# IR.net
KiCad netlist of a schematic drawn in EAGLE
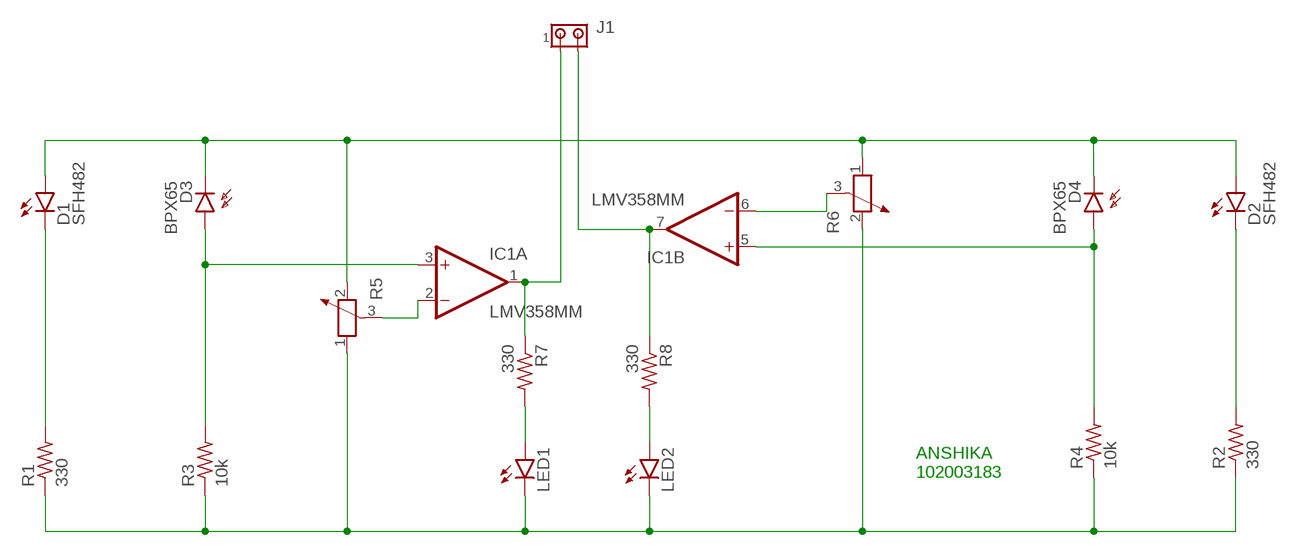
[diagram p0: schematic, sheet 1]

(export (version "E")
  (design (tool "Eeschema 10.0.6"))
  (components
    (comp (ref "D1")
      (value "SFH482")
      (footprint "eagle-import:SFH482")
      (libsource (lib "eagle-import") (part "SFH482"))
    )
    (comp (ref "D2")
      (value "SFH482")
      (footprint "eagle-import:SFH482")
      (libsource (lib "eagle-import") (part "SFH482"))
    )
    (comp (ref "D3")
      (value "BPX65")
      (footprint "eagle-import:BPX65")
      (fields (field (name "MPN") "BPX65."))
      (libsource (lib "eagle-import") (part "BPX65"))
    )
    (comp (ref "D4")
      (value "BPX65")
      (footprint "eagle-import:BPX65")
      (fields (field (name "MPN") "BPX65."))
      (libsource (lib "eagle-import") (part "BPX65"))
    )
    (comp (ref "IC1")
      (value "LMV358MM")
      (footprint "eagle-import:MSOP08")
      (libsource (lib "eagle-import") (part "LMV358?MM"))
    )
    (comp (ref "J1")
      (value "MTA02-100")
      (footprint "eagle-import:10X02MTA")
      (libsource (lib "eagle-import") (part "MTA02-100"))
    )
    (comp (ref "LED1")
      (value "LED3MM")
      (footprint "eagle-import:LED3MM")
      (libsource (lib "eagle-import") (part "LED3MM"))
    )
    (comp (ref "LED2")
      (value "LED3MM")
      (footprint "eagle-import:LED3MM")
      (libsource (lib "eagle-import") (part "LED3MM"))
    )
    (comp (ref "R1")
      (value "330")
      (footprint "eagle-import:0207_10")
      (libsource (lib "eagle-import") (part "R-US_0207/10"))
    )
    (comp (ref "R2")
      (value "330")
      (footprint "eagle-import:0207_10")
      (libsource (lib "eagle-import") (part "R-US_0207/10"))
    )
    (comp (ref "R3")
      (value "10k")
      (footprint "eagle-import:0207_10")
      (libsource (lib "eagle-import") (part "R-US_0207/10"))
    )
    (comp (ref "R4")
      (value "10k")
      (footprint "eagle-import:0207_10")
      (libsource (lib "eagle-import") (part "R-US_0207/10"))
    )
    (comp (ref "R5")
      (value "POTENTIOMETER_PT-10S")
      (footprint "eagle-import:PT-10S")
      (libsource (lib "eagle-import") (part "POTENTIOMETER_PT-10S"))
    )
    (comp (ref "R6")
      (value "POTENTIOMETER_PT-10S")
      (footprint "eagle-import:PT-10S")
      (libsource (lib "eagle-import") (part "POTENTIOMETER_PT-10S"))
    )
    (comp (ref "R7")
      (value "330")
      (footprint "eagle-import:0207_10")
      (libsource (lib "eagle-import") (part "R-US_0207/10"))
    )
    (comp (ref "R8")
      (value "330")
      (footprint "eagle-import:0207_10")
      (libsource (lib "eagle-import") (part "R-US_0207/10"))
    )
  )
  (nets
    (net (code "1") (name "Net-(D1-C)") (class "Default")
      (node (ref "D1") (pin "K") (pinfunction "C_K") (pintype "passive"))
      (node (ref "R1") (pin "2") (pinfunction "2_2") (pintype "passive"))
    )
    (net (code "2") (name "Net-(D2-C)") (class "Default")
      (node (ref "D2") (pin "K") (pinfunction "C_K") (pintype "passive"))
      (node (ref "R2") (pin "2") (pinfunction "2_2") (pintype "passive"))
    )
    (net (code "3") (name "Net-(D3-C)") (class "Default")
      (node (ref "D1") (pin "A") (pinfunction "A_A") (pintype "passive"))
      (node (ref "D2") (pin "A") (pinfunction "A_A") (pintype "passive"))
      (node (ref "D3") (pin "K") (pinfunction "C_K") (pintype "passive"))
      (node (ref "D4") (pin "K") (pinfunction "C_K") (pintype "passive"))
      (node (ref "R5") (pin "2") (pinfunction "2_2") (pintype "passive"))
      (node (ref "R6") (pin "1") (pinfunction "1_1") (pintype "passive"))
    )
    (net (code "4") (name "Net-(IC1A-+IN)") (class "Default")
      (node (ref "D3") (pin "A") (pinfunction "A_A") (pintype "passive"))
      (node (ref "IC1") (pin "3") (pinfunction "+IN_3") (pintype "input"))
      (node (ref "R3") (pin "2") (pinfunction "2_2") (pintype "passive"))
    )
    (net (code "5") (name "Net-(IC1A--IN)") (class "Default")
      (node (ref "IC1") (pin "2") (pinfunction "-IN_2") (pintype "input"))
      (node (ref "R5") (pin "3") (pinfunction "3_3") (pintype "passive"))
    )
    (net (code "6") (name "Net-(IC1A-OUT)") (class "Default")
      (node (ref "IC1") (pin "1") (pinfunction "OUT_1") (pintype "output"))
      (node (ref "J1") (pin "1") (pinfunction "1_1") (pintype "passive"))
      (node (ref "R7") (pin "1") (pinfunction "1_1") (pintype "passive"))
    )
    (net (code "7") (name "Net-(IC1B-+IN)") (class "Default")
      (node (ref "D4") (pin "A") (pinfunction "A_A") (pintype "passive"))
      (node (ref "IC1") (pin "5") (pinfunction "+IN_5") (pintype "input"))
      (node (ref "R4") (pin "2") (pinfunction "2_2") (pintype "passive"))
    )
    (net (code "8") (name "Net-(IC1B--IN)") (class "Default")
      (node (ref "IC1") (pin "6") (pinfunction "-IN_6") (pintype "input"))
      (node (ref "R6") (pin "3") (pinfunction "3_3") (pintype "passive"))
    )
    (net (code "9") (name "Net-(IC1B-OUT)") (class "Default")
      (node (ref "IC1") (pin "7") (pinfunction "OUT_7") (pintype "output"))
      (node (ref "J1") (pin "2") (pinfunction "2_2") (pintype "passive"))
      (node (ref "R8") (pin "1") (pinfunction "1_1") (pintype "passive"))
    )
    (net (code "10") (name "Net-(LED1-C)") (class "Default")
      (node (ref "LED1") (pin "K") (pinfunction "C_K") (pintype "passive"))
      (node (ref "LED2") (pin "K") (pinfunction "C_K") (pintype "passive"))
      (node (ref "R1") (pin "1") (pinfunction "1_1") (pintype "passive"))
      (node (ref "R2") (pin "1") (pinfunction "1_1") (pintype "passive"))
      (node (ref "R3") (pin "1") (pinfunction "1_1") (pintype "passive"))
      (node (ref "R4") (pin "1") (pinfunction "1_1") (pintype "passive"))
      (node (ref "R5") (pin "1") (pinfunction "1_1") (pintype "passive"))
      (node (ref "R6") (pin "2") (pinfunction "2_2") (pintype "passive"))
    )
    (net (code "11") (name "Net-(LED1-PadA)") (class "Default")
      (node (ref "LED1") (pin "A") (pinfunction "A_A") (pintype "passive"))
      (node (ref "R7") (pin "2") (pinfunction "2_2") (pintype "passive"))
    )
    (net (code "12") (name "Net-(LED2-PadA)") (class "Default")
      (node (ref "LED2") (pin "A") (pinfunction "A_A") (pintype "passive"))
      (node (ref "R8") (pin "2") (pinfunction "2_2") (pintype "passive"))
    )
  )
)
